# obc-v2_MCU-PinOut.net
KiCad netlist of a schematic drawn in Altium Designer
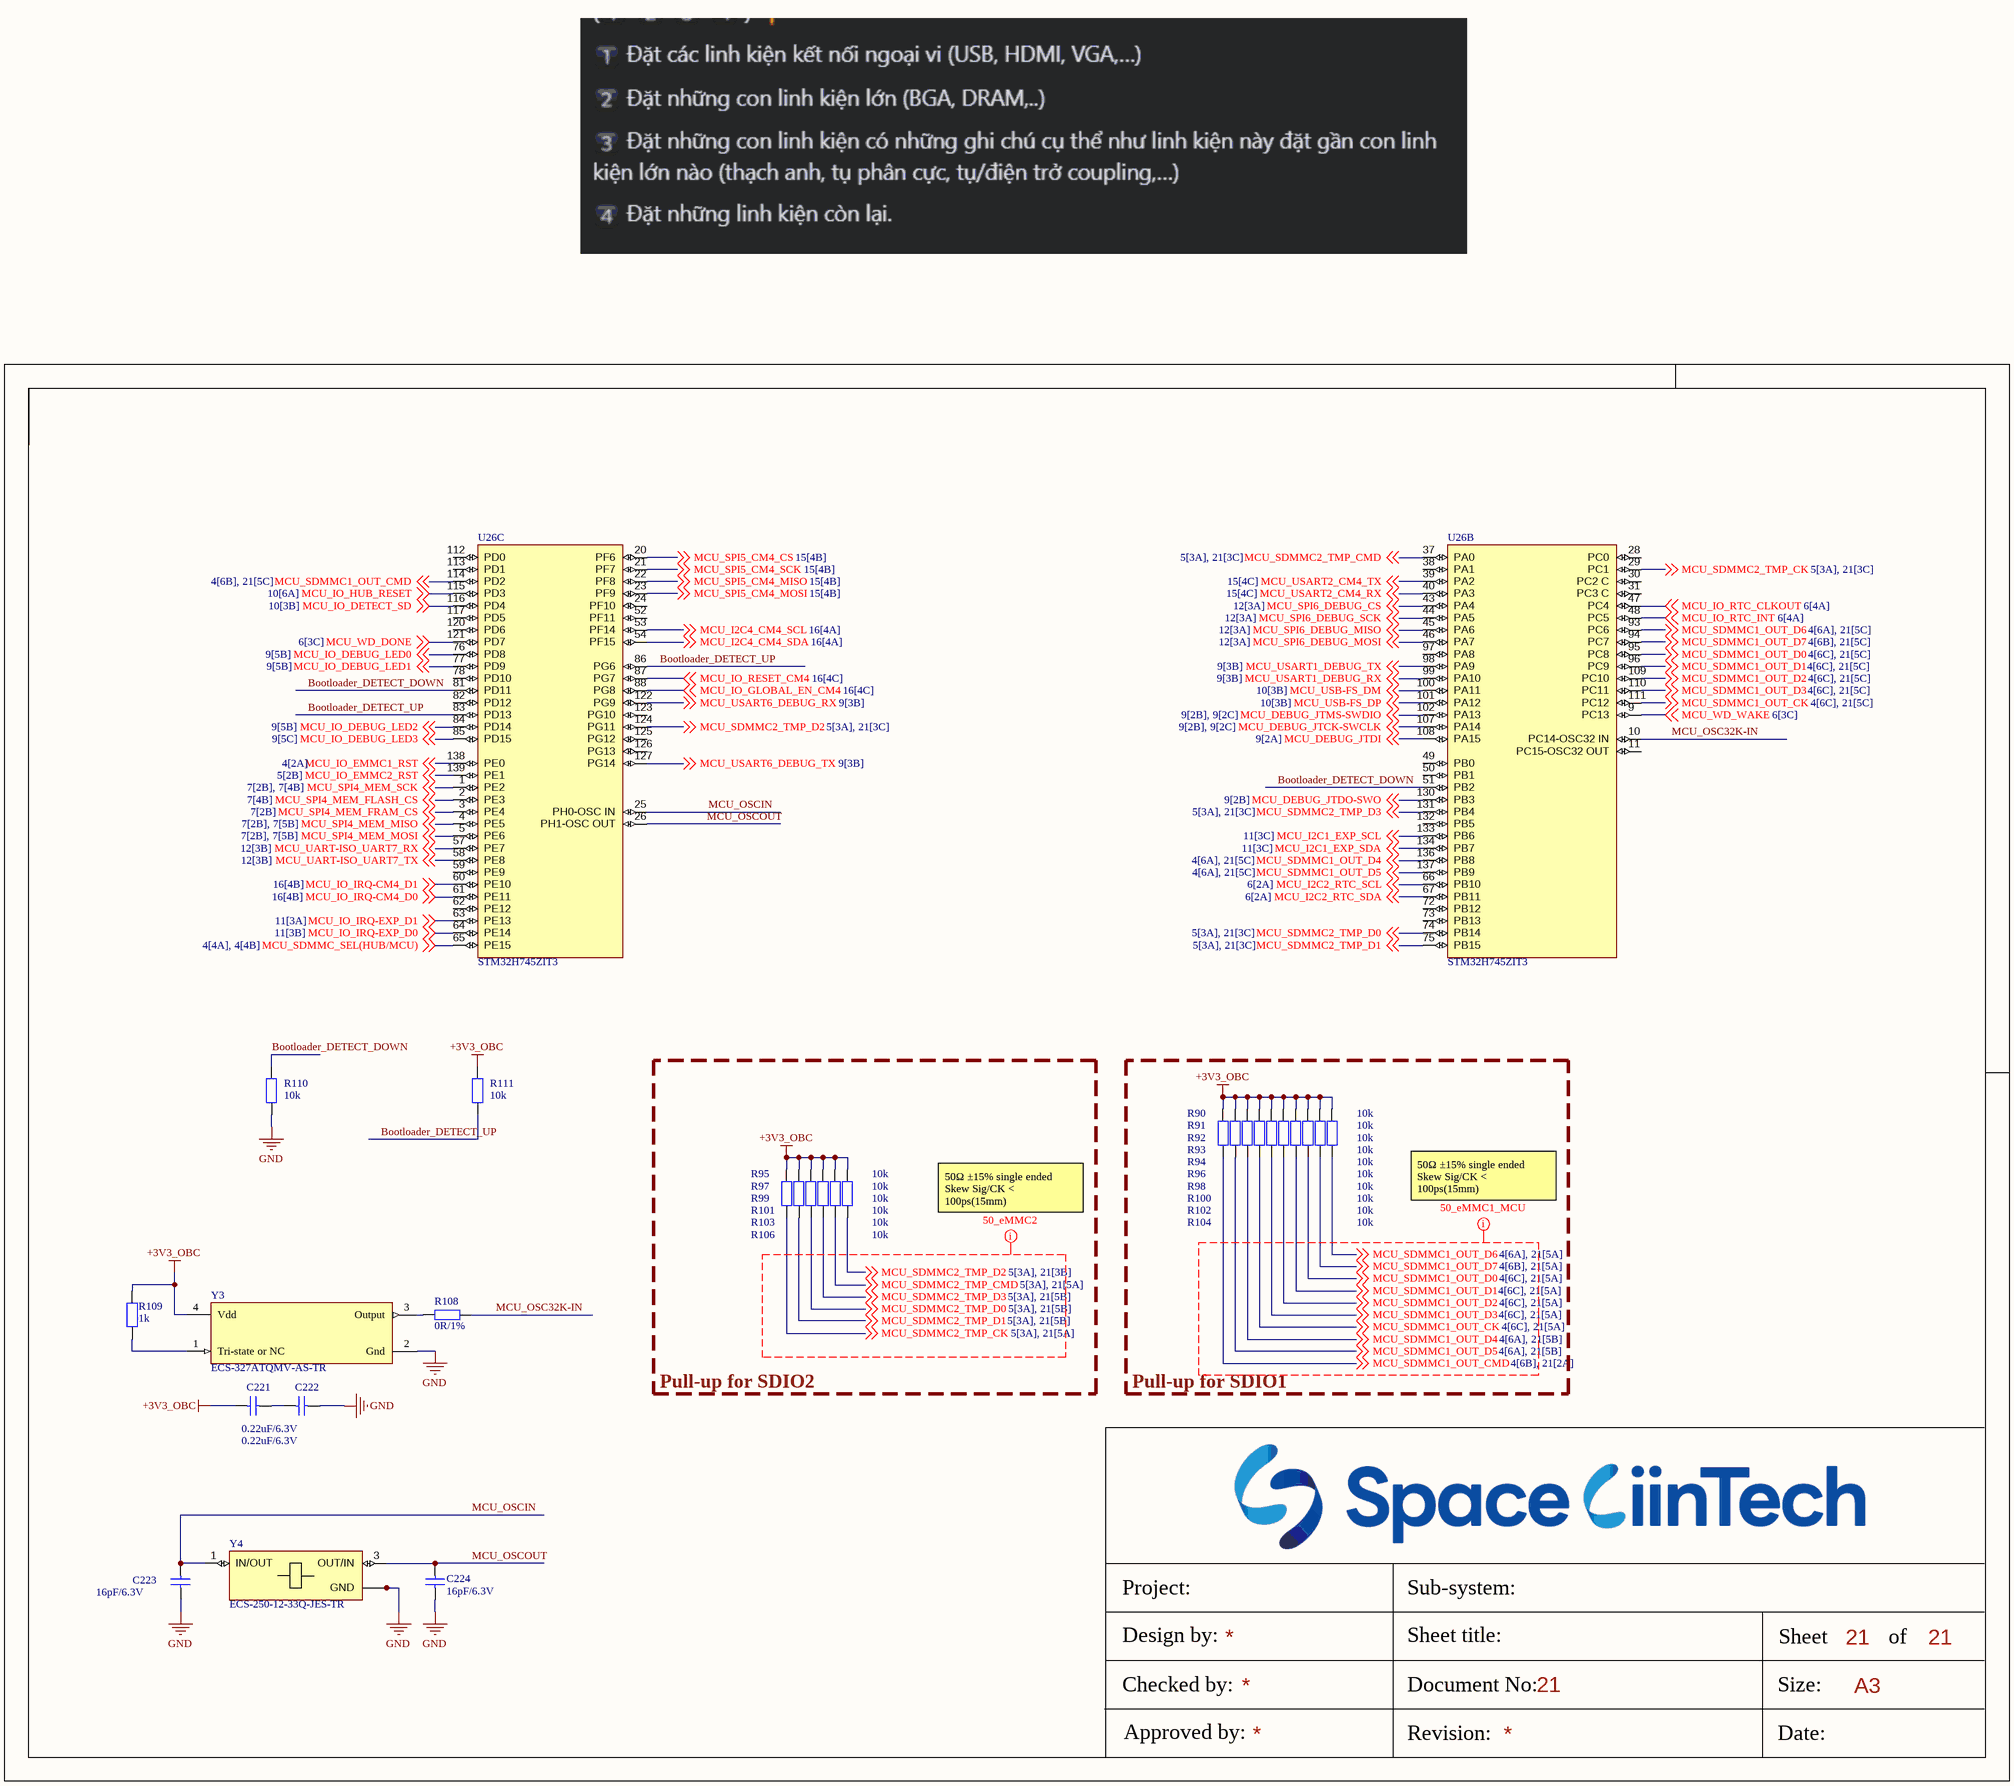
[diagram p0: obc-v2_MCU-PinOut.SchDoc]

(export (version "E")
  (design (tool "Eeschema 10.0.6"))
  (components
    (comp (ref "C221")
      (value "0.22uF/6.3V")
      (footprint "CAP_C_1005X60")
      (description "CAPC")
      (libsource (lib "Altium_Lib_by_KhueNguyenCreator") (part "Tu 0402 33nF 10V"))
    )
    (comp (ref "C222")
      (value "0.22uF/6.3V")
      (footprint "CAP_C_1005X60")
      (description "CAPC")
      (libsource (lib "Altium_Lib_by_KhueNguyenCreator") (part "Tu 0402 33nF 10V"))
    )
    (comp (ref "C223")
      (value "16pF/6.3V")
      (footprint "CAP_C_1005X60")
      (description "CAPC")
      (libsource (lib "Altium_Lib_by_KhueNguyenCreator") (part "Tu 0402 33nF 10V"))
    )
    (comp (ref "C224")
      (value "16pF/6.3V")
      (footprint "CAP_C_1005X60")
      (description "CAPC")
      (libsource (lib "Altium_Lib_by_KhueNguyenCreator") (part "Tu 0402 33nF 10V"))
    )
    (comp (ref "R90")
      (value "10k")
      (footprint "RES_C_1608X60")
      (description "RES 4.7K OHM 1% 1/10W 0603, P/N: ERJ-U03F4701V")
      (libsource (lib "Altium_Lib_by_KhueNguyenCreator") (part "Tro 0603 1% 10k"))
    )
    (comp (ref "R91")
      (value "10k")
      (footprint "RES_C_1608X60")
      (description "RES 4.7K OHM 1% 1/10W 0603, P/N: ERJ-U03F4701V")
      (libsource (lib "Altium_Lib_by_KhueNguyenCreator") (part "Tro 0603 1% 10k"))
    )
    (comp (ref "R92")
      (value "10k")
      (footprint "RES_C_1608X60")
      (description "RES 4.7K OHM 1% 1/10W 0603, P/N: ERJ-U03F4701V")
      (libsource (lib "Altium_Lib_by_KhueNguyenCreator") (part "Tro 0603 1% 10k"))
    )
    (comp (ref "R93")
      (value "10k")
      (footprint "RES_C_1608X60")
      (description "RES 4.7K OHM 1% 1/10W 0603, P/N: ERJ-U03F4701V")
      (libsource (lib "Altium_Lib_by_KhueNguyenCreator") (part "Tro 0603 1% 10k"))
    )
    (comp (ref "R94")
      (value "10k")
      (footprint "RES_C_1608X60")
      (description "RES 4.7K OHM 1% 1/10W 0603, P/N: ERJ-U03F4701V")
      (libsource (lib "Altium_Lib_by_KhueNguyenCreator") (part "Tro 0603 1% 10k"))
    )
    (comp (ref "R95")
      (value "10k")
      (footprint "RES_C_1608X60")
      (description "RES 4.7K OHM 1% 1/10W 0603, P/N: ERJ-U03F4701V")
      (libsource (lib "Altium_Lib_by_KhueNguyenCreator") (part "Tro 0603 1% 10k"))
    )
    (comp (ref "R96")
      (value "10k")
      (footprint "RES_C_1608X60")
      (description "RES 4.7K OHM 1% 1/10W 0603, P/N: ERJ-U03F4701V")
      (libsource (lib "Altium_Lib_by_KhueNguyenCreator") (part "Tro 0603 1% 10k"))
    )
    (comp (ref "R97")
      (value "10k")
      (footprint "RES_C_1608X60")
      (description "RES 4.7K OHM 1% 1/10W 0603, P/N: ERJ-U03F4701V")
      (libsource (lib "Altium_Lib_by_KhueNguyenCreator") (part "Tro 0603 1% 10k"))
    )
    (comp (ref "R98")
      (value "10k")
      (footprint "RES_C_1608X60")
      (description "RES 4.7K OHM 1% 1/10W 0603, P/N: ERJ-U03F4701V")
      (libsource (lib "Altium_Lib_by_KhueNguyenCreator") (part "Tro 0603 1% 10k"))
    )
    (comp (ref "R99")
      (value "10k")
      (footprint "RES_C_1608X60")
      (description "RES 4.7K OHM 1% 1/10W 0603, P/N: ERJ-U03F4701V")
      (libsource (lib "Altium_Lib_by_KhueNguyenCreator") (part "Tro 0603 1% 10k"))
    )
    (comp (ref "R100")
      (value "10k")
      (footprint "RES_C_1608X60")
      (description "RES 4.7K OHM 1% 1/10W 0603, P/N: ERJ-U03F4701V")
      (libsource (lib "Altium_Lib_by_KhueNguyenCreator") (part "Tro 0603 1% 10k"))
    )
    (comp (ref "R101")
      (value "10k")
      (footprint "RES_C_1608X60")
      (description "RES 4.7K OHM 1% 1/10W 0603, P/N: ERJ-U03F4701V")
      (libsource (lib "Altium_Lib_by_KhueNguyenCreator") (part "Tro 0603 1% 10k"))
    )
    (comp (ref "R102")
      (value "10k")
      (footprint "RES_C_1608X60")
      (description "RES 4.7K OHM 1% 1/10W 0603, P/N: ERJ-U03F4701V")
      (libsource (lib "Altium_Lib_by_KhueNguyenCreator") (part "Tro 0603 1% 10k"))
    )
    (comp (ref "R103")
      (value "10k")
      (footprint "RES_C_1608X60")
      (description "RES 4.7K OHM 1% 1/10W 0603, P/N: ERJ-U03F4701V")
      (libsource (lib "Altium_Lib_by_KhueNguyenCreator") (part "Tro 0603 1% 10k"))
    )
    (comp (ref "R104")
      (value "10k")
      (footprint "RES_C_1608X60")
      (description "RES 4.7K OHM 1% 1/10W 0603, P/N: ERJ-U03F4701V")
      (libsource (lib "Altium_Lib_by_KhueNguyenCreator") (part "Tro 0603 1% 10k"))
    )
    (comp (ref "R106")
      (value "10k")
      (footprint "RES_C_1608X60")
      (description "RES 4.7K OHM 1% 1/10W 0603, P/N: ERJ-U03F4701V")
      (libsource (lib "Altium_Lib_by_KhueNguyenCreator") (part "Tro 0603 1% 10k"))
    )
    (comp (ref "R108")
      (value "0R/1%")
      (footprint "RES_C_1608X60")
      (description "RES")
      (libsource (lib "Altium_Lib_by_KhueNguyenCreator") (part "Tro 0603 1% 10k"))
    )
    (comp (ref "R109")
      (value "1k")
      (footprint "RES_C_1608X60")
      (description "RES")
      (libsource (lib "Altium_Lib_by_KhueNguyenCreator") (part "Tro 0603 1% 10k"))
    )
    (comp (ref "R110")
      (value "10k")
      (footprint "RES_C_1608X60")
      (description "RES 4.7K OHM 1% 1/10W 0603, P/N: ERJ-U03F4701V")
      (libsource (lib "Altium_Lib_by_KhueNguyenCreator") (part "Tro 0603 1% 10k"))
    )
    (comp (ref "R111")
      (value "10k")
      (footprint "RES_C_1608X60")
      (description "RES 4.7K OHM 1% 1/10W 0603, P/N: ERJ-U03F4701V")
      (libsource (lib "Altium_Lib_by_KhueNguyenCreator") (part "Tro 0603 1% 10k"))
    )
    (comp (ref "U26")
      (value "STM32H745ZIT3")
      (footprint "FP-LQFP144-1A-MFG")
      (description "HIGH-PERFORMANCE AND DSP WITH DP")
      (fields
        (field (name "MANUFACTURER PART NUMBER") "STM32H745ZIT6")
        (field (name "OCTOPART") "https://octopart.com/stm32h745zit6-stmicroelectronics-100293939")
      )
      (libsource (lib "Altium Content Vault") (part "f5432ce9894f79c0085309acf87c031"))
    )
    (comp (ref "Y3")
      (value "ECS-327ATQMV-AS-TR")
      (footprint "FP-327ATQMV-MFG")
      (description "XTAL OSC XO 32.7680KHZ CMOS SMD")
      (libsource (lib "Altium Content Vault") (part "48575ee33648fc99c8f9879a7ebcfb2"))
    )
    (comp (ref "Y4")
      (value "ECS-250-12-33Q-JES-TR")
      (footprint "XTAL_ECS-250-12-33Q-JES-TR")
      (description "25 MHz Â±20ppm Crystal 12pF 40 Ohms 4-SMD, No Lead")
      (fields (field (name "MF") "ECS Inc."))
      (libsource (lib "ECS-250-12-33Q-JES-TR") (part "ECS-250-12-33Q-JES-TR"))
    )
  )
  (nets
    (net (code "1") (name "+3V3_OBC") (class "Default")
      (node (ref "C221") (pin "1") (pinfunction "1_1") (pintype "passive"))
      (node (ref "R100") (pin "2") (pinfunction "2_2") (pintype "passive"))
      (node (ref "R101") (pin "2") (pinfunction "2_2") (pintype "passive"))
      (node (ref "R102") (pin "2") (pinfunction "2_2") (pintype "passive"))
      (node (ref "R103") (pin "2") (pinfunction "2_2") (pintype "passive"))
      (node (ref "R104") (pin "2") (pinfunction "2_2") (pintype "passive"))
      (node (ref "R106") (pin "2") (pinfunction "2_2") (pintype "passive"))
      (node (ref "R109") (pin "1") (pinfunction "1_1") (pintype "passive"))
      (node (ref "R111") (pin "2") (pinfunction "2_2") (pintype "passive"))
      (node (ref "R90") (pin "2") (pinfunction "2_2") (pintype "passive"))
      (node (ref "R91") (pin "2") (pinfunction "2_2") (pintype "passive"))
      (node (ref "R92") (pin "2") (pinfunction "2_2") (pintype "passive"))
      (node (ref "R93") (pin "2") (pinfunction "2_2") (pintype "passive"))
      (node (ref "R94") (pin "2") (pinfunction "2_2") (pintype "passive"))
      (node (ref "R95") (pin "2") (pinfunction "2_2") (pintype "passive"))
      (node (ref "R96") (pin "2") (pinfunction "2_2") (pintype "passive"))
      (node (ref "R97") (pin "2") (pinfunction "2_2") (pintype "passive"))
      (node (ref "R98") (pin "2") (pinfunction "2_2") (pintype "passive"))
      (node (ref "R99") (pin "2") (pinfunction "2_2") (pintype "passive"))
      (node (ref "Y3") (pin "4") (pinfunction "Vdd_4") (pintype "power_in"))
    )
    (net (code "2") (name "/Bootloader_DETECT_DOWN") (class "Default")
      (node (ref "R110") (pin "2") (pinfunction "2_2") (pintype "passive"))
      (node (ref "U26") (pin "51") (pinfunction "PB2_51") (pintype "bidirectional"))
      (node (ref "U26") (pin "81") (pinfunction "PD11_81") (pintype "bidirectional"))
    )
    (net (code "3") (name "/Bootloader_DETECT_UP") (class "Default")
      (node (ref "R111") (pin "1") (pinfunction "1_1") (pintype "passive"))
      (node (ref "U26") (pin "83") (pinfunction "PD13_83") (pintype "bidirectional"))
      (node (ref "U26") (pin "86") (pinfunction "PG6_86") (pintype "bidirectional"))
    )
    (net (code "4") (name "/MCU_OSC32K-IN") (class "Default")
      (node (ref "R108") (pin "1") (pinfunction "1_1") (pintype "passive"))
      (node (ref "U26") (pin "10") (pinfunction "PC14-OSC32_IN_10") (pintype "bidirectional"))
    )
    (net (code "5") (name "/MCU_OSCIN") (class "Default")
      (node (ref "C223") (pin "2") (pinfunction "2_2") (pintype "passive"))
      (node (ref "U26") (pin "25") (pinfunction "PH0-OSC_IN_25") (pintype "bidirectional"))
      (node (ref "Y4") (pin "1") (pinfunction "IN/OUT_1") (pintype "bidirectional"))
    )
    (net (code "6") (name "/MCU_OSCOUT") (class "Default")
      (node (ref "C224") (pin "2") (pinfunction "2_2") (pintype "passive"))
      (node (ref "U26") (pin "26") (pinfunction "PH1-OSC_OUT_26") (pintype "bidirectional"))
      (node (ref "Y4") (pin "3") (pinfunction "OUT/IN_3") (pintype "bidirectional"))
    )
    (net (code "7") (name "GND") (class "Default")
      (node (ref "C222") (pin "2") (pinfunction "2_2") (pintype "passive"))
      (node (ref "C223") (pin "1") (pinfunction "1_1") (pintype "passive"))
      (node (ref "C224") (pin "1") (pinfunction "1_1") (pintype "passive"))
      (node (ref "R110") (pin "1") (pinfunction "1_1") (pintype "passive"))
      (node (ref "Y3") (pin "2") (pinfunction "Gnd_2") (pintype "power_in"))
      (node (ref "Y4") (pin "2") (pinfunction "GND_2") (pintype "power_in"))
      (node (ref "Y4") (pin "4") (pinfunction "GND_4") (pintype "power_in"))
    )
    (net (code "8") (name "MCU_DEBUG_JTCK-SWCLK") (class "Default")
      (node (ref "U26") (pin "107") (pinfunction "PA14_107") (pintype "bidirectional"))
    )
    (net (code "9") (name "MCU_DEBUG_JTDI") (class "Default")
      (node (ref "U26") (pin "108") (pinfunction "PA15_108") (pintype "bidirectional"))
    )
    (net (code "10") (name "MCU_DEBUG_JTDO-SWO") (class "Default")
      (node (ref "U26") (pin "130") (pinfunction "PB3_130") (pintype "bidirectional"))
    )
    (net (code "11") (name "MCU_DEBUG_JTMS-SWDIO") (class "Default")
      (node (ref "U26") (pin "102") (pinfunction "PA13_102") (pintype "bidirectional"))
    )
    (net (code "12") (name "MCU_I2C1_EXP_SCL") (class "Default")
      (node (ref "U26") (pin "133") (pinfunction "PB6_133") (pintype "bidirectional"))
    )
    (net (code "13") (name "MCU_I2C1_EXP_SDA") (class "Default")
      (node (ref "U26") (pin "134") (pinfunction "PB7_134") (pintype "bidirectional"))
    )
    (net (code "14") (name "MCU_I2C2_RTC_SCL") (class "Default")
      (node (ref "U26") (pin "66") (pinfunction "PB10_66") (pintype "bidirectional"))
    )
    (net (code "15") (name "MCU_I2C2_RTC_SDA") (class "Default")
      (node (ref "U26") (pin "67") (pinfunction "PB11_67") (pintype "bidirectional"))
    )
    (net (code "16") (name "MCU_I2C4_CM4_SCL") (class "Default")
      (node (ref "U26") (pin "53") (pinfunction "PF14_53") (pintype "bidirectional"))
    )
    (net (code "17") (name "MCU_I2C4_CM4_SDA") (class "Default")
      (node (ref "U26") (pin "54") (pinfunction "PF15_54") (pintype "bidirectional"))
    )
    (net (code "18") (name "MCU_IO_DEBUG_LED0") (class "Default")
      (node (ref "U26") (pin "76") (pinfunction "PD8_76") (pintype "bidirectional"))
    )
    (net (code "19") (name "MCU_IO_DEBUG_LED1") (class "Default")
      (node (ref "U26") (pin "77") (pinfunction "PD9_77") (pintype "bidirectional"))
    )
    (net (code "20") (name "MCU_IO_DEBUG_LED2") (class "Default")
      (node (ref "U26") (pin "84") (pinfunction "PD14_84") (pintype "bidirectional"))
    )
    (net (code "21") (name "MCU_IO_DEBUG_LED3") (class "Default")
      (node (ref "U26") (pin "85") (pinfunction "PD15_85") (pintype "bidirectional"))
    )
    (net (code "22") (name "MCU_IO_DETECT_SD") (class "Default")
      (node (ref "U26") (pin "116") (pinfunction "PD4_116") (pintype "bidirectional"))
    )
    (net (code "23") (name "MCU_IO_EMMC1_RST") (class "Default")
      (node (ref "U26") (pin "138") (pinfunction "PE0_138") (pintype "bidirectional"))
    )
    (net (code "24") (name "MCU_IO_EMMC2_RST") (class "Default")
      (node (ref "U26") (pin "139") (pinfunction "PE1_139") (pintype "bidirectional"))
    )
    (net (code "25") (name "MCU_IO_GLOBAL_EN_CM4") (class "Default")
      (node (ref "U26") (pin "88") (pinfunction "PG8_88") (pintype "bidirectional"))
    )
    (net (code "26") (name "MCU_IO_HUB_RESET") (class "Default")
      (node (ref "U26") (pin "115") (pinfunction "PD3_115") (pintype "bidirectional"))
    )
    (net (code "27") (name "MCU_IO_IRQ-CM4_D0") (class "Default")
      (node (ref "U26") (pin "61") (pinfunction "PE11_61") (pintype "bidirectional"))
    )
    (net (code "28") (name "MCU_IO_IRQ-CM4_D1") (class "Default")
      (node (ref "U26") (pin "60") (pinfunction "PE10_60") (pintype "bidirectional"))
    )
    (net (code "29") (name "MCU_IO_IRQ-EXP_D0") (class "Default")
      (node (ref "U26") (pin "64") (pinfunction "PE14_64") (pintype "bidirectional"))
    )
    (net (code "30") (name "MCU_IO_IRQ-EXP_D1") (class "Default")
      (node (ref "U26") (pin "63") (pinfunction "PE13_63") (pintype "bidirectional"))
    )
    (net (code "31") (name "MCU_IO_RESET_CM4") (class "Default")
      (node (ref "U26") (pin "87") (pinfunction "PG7_87") (pintype "bidirectional"))
    )
    (net (code "32") (name "MCU_IO_RTC_CLKOUT") (class "Default")
      (node (ref "U26") (pin "47") (pinfunction "PC4_47") (pintype "bidirectional"))
    )
    (net (code "33") (name "MCU_IO_RTC_INT") (class "Default")
      (node (ref "U26") (pin "48") (pinfunction "PC5_48") (pintype "bidirectional"))
    )
    (net (code "34") (name "MCU_SDMMC1_OUT_CK") (class "Default")
      (node (ref "R93") (pin "1") (pinfunction "1_1") (pintype "passive"))
      (node (ref "U26") (pin "111") (pinfunction "PC12_111") (pintype "bidirectional"))
    )
    (net (code "35") (name "MCU_SDMMC1_OUT_CMD") (class "Default")
      (node (ref "R90") (pin "1") (pinfunction "1_1") (pintype "passive"))
      (node (ref "U26") (pin "114") (pinfunction "PD2_114") (pintype "bidirectional"))
    )
    (net (code "36") (name "MCU_SDMMC1_OUT_D0") (class "Default")
      (node (ref "R100") (pin "1") (pinfunction "1_1") (pintype "passive"))
      (node (ref "U26") (pin "95") (pinfunction "PC8_95") (pintype "bidirectional"))
    )
    (net (code "37") (name "MCU_SDMMC1_OUT_D1") (class "Default")
      (node (ref "R98") (pin "1") (pinfunction "1_1") (pintype "passive"))
      (node (ref "U26") (pin "96") (pinfunction "PC9_96") (pintype "bidirectional"))
    )
    (net (code "38") (name "MCU_SDMMC1_OUT_D2") (class "Default")
      (node (ref "R96") (pin "1") (pinfunction "1_1") (pintype "passive"))
      (node (ref "U26") (pin "109") (pinfunction "PC10_109") (pintype "bidirectional"))
    )
    (net (code "39") (name "MCU_SDMMC1_OUT_D3") (class "Default")
      (node (ref "R94") (pin "1") (pinfunction "1_1") (pintype "passive"))
      (node (ref "U26") (pin "110") (pinfunction "PC11_110") (pintype "bidirectional"))
    )
    (net (code "40") (name "MCU_SDMMC1_OUT_D4") (class "Default")
      (node (ref "R92") (pin "1") (pinfunction "1_1") (pintype "passive"))
      (node (ref "U26") (pin "136") (pinfunction "PB8_136") (pintype "bidirectional"))
    )
    (net (code "41") (name "MCU_SDMMC1_OUT_D5") (class "Default")
      (node (ref "R91") (pin "1") (pinfunction "1_1") (pintype "passive"))
      (node (ref "U26") (pin "137") (pinfunction "PB9_137") (pintype "bidirectional"))
    )
    (net (code "42") (name "MCU_SDMMC1_OUT_D6") (class "Default")
      (node (ref "R104") (pin "1") (pinfunction "1_1") (pintype "passive"))
      (node (ref "U26") (pin "93") (pinfunction "PC6_93") (pintype "bidirectional"))
    )
    (net (code "43") (name "MCU_SDMMC1_OUT_D7") (class "Default")
      (node (ref "R102") (pin "1") (pinfunction "1_1") (pintype "passive"))
      (node (ref "U26") (pin "94") (pinfunction "PC7_94") (pintype "bidirectional"))
    )
    (net (code "44") (name "MCU_SDMMC2_TMP_CK") (class "Default")
      (node (ref "R95") (pin "1") (pinfunction "1_1") (pintype "passive"))
      (node (ref "U26") (pin "29") (pinfunction "PC1_29") (pintype "bidirectional"))
    )
    (net (code "45") (name "MCU_SDMMC2_TMP_CMD") (class "Default")
      (node (ref "R103") (pin "1") (pinfunction "1_1") (pintype "passive"))
      (node (ref "U26") (pin "37") (pinfunction "PA0_37") (pintype "bidirectional"))
    )
    (net (code "46") (name "MCU_SDMMC2_TMP_D0") (class "Default")
      (node (ref "R99") (pin "1") (pinfunction "1_1") (pintype "passive"))
      (node (ref "U26") (pin "74") (pinfunction "PB14_74") (pintype "bidirectional"))
    )
    (net (code "47") (name "MCU_SDMMC2_TMP_D1") (class "Default")
      (node (ref "R97") (pin "1") (pinfunction "1_1") (pintype "passive"))
      (node (ref "U26") (pin "75") (pinfunction "PB15_75") (pintype "bidirectional"))
    )
    (net (code "48") (name "MCU_SDMMC2_TMP_D2") (class "Default")
      (node (ref "R106") (pin "1") (pinfunction "1_1") (pintype "passive"))
      (node (ref "U26") (pin "124") (pinfunction "PG11_124") (pintype "bidirectional"))
    )
    (net (code "49") (name "MCU_SDMMC2_TMP_D3") (class "Default")
      (node (ref "R101") (pin "1") (pinfunction "1_1") (pintype "passive"))
      (node (ref "U26") (pin "131") (pinfunction "PB4_131") (pintype "bidirectional"))
    )
    (net (code "50") (name "MCU_SDMMC_SEL(HUB{slash}MCU)") (class "Default")
      (node (ref "U26") (pin "65") (pinfunction "PE15_65") (pintype "bidirectional"))
    )
    (net (code "51") (name "MCU_SPI4_MEM_FLASH_CS") (class "Default")
      (node (ref "U26") (pin "2") (pinfunction "PE3_2") (pintype "bidirectional"))
    )
    (net (code "52") (name "MCU_SPI4_MEM_FRAM_CS") (class "Default")
      (node (ref "U26") (pin "3") (pinfunction "PE4_3") (pintype "bidirectional"))
    )
    (net (code "53") (name "MCU_SPI4_MEM_MISO") (class "Default")
      (node (ref "U26") (pin "4") (pinfunction "PE5_4") (pintype "bidirectional"))
    )
    (net (code "54") (name "MCU_SPI4_MEM_MOSI") (class "Default")
      (node (ref "U26") (pin "5") (pinfunction "PE6_5") (pintype "bidirectional"))
    )
    (net (code "55") (name "MCU_SPI4_MEM_SCK") (class "Default")
      (node (ref "U26") (pin "1") (pinfunction "PE2_1") (pintype "bidirectional"))
    )
    (net (code "56") (name "MCU_SPI5_CM4_CS") (class "Default")
      (node (ref "U26") (pin "20") (pinfunction "PF6_20") (pintype "bidirectional"))
    )
    (net (code "57") (name "MCU_SPI5_CM4_MISO") (class "Default")
      (node (ref "U26") (pin "22") (pinfunction "PF8_22") (pintype "bidirectional"))
    )
    (net (code "58") (name "MCU_SPI5_CM4_MOSI") (class "Default")
      (node (ref "U26") (pin "23") (pinfunction "PF9_23") (pintype "bidirectional"))
    )
    (net (code "59") (name "MCU_SPI5_CM4_SCK") (class "Default")
      (node (ref "U26") (pin "21") (pinfunction "PF7_21") (pintype "bidirectional"))
    )
    (net (code "60") (name "MCU_SPI6_DEBUG_CS") (class "Default")
      (node (ref "U26") (pin "43") (pinfunction "PA4_43") (pintype "bidirectional"))
    )
    (net (code "61") (name "MCU_SPI6_DEBUG_MISO") (class "Default")
      (node (ref "U26") (pin "45") (pinfunction "PA6_45") (pintype "bidirectional"))
    )
    (net (code "62") (name "MCU_SPI6_DEBUG_MOSI") (class "Default")
      (node (ref "U26") (pin "46") (pinfunction "PA7_46") (pintype "bidirectional"))
    )
    (net (code "63") (name "MCU_SPI6_DEBUG_SCK") (class "Default")
      (node (ref "U26") (pin "44") (pinfunction "PA5_44") (pintype "bidirectional"))
    )
    (net (code "64") (name "MCU_UART-ISO_UART7_RX") (class "Default")
      (node (ref "U26") (pin "57") (pinfunction "PE7_57") (pintype "bidirectional"))
    )
    (net (code "65") (name "MCU_UART-ISO_UART7_TX") (class "Default")
      (node (ref "U26") (pin "58") (pinfunction "PE8_58") (pintype "bidirectional"))
    )
    (net (code "66") (name "MCU_USART1_DEBUG_RX") (class "Default")
      (node (ref "U26") (pin "99") (pinfunction "PA10_99") (pintype "bidirectional"))
    )
    (net (code "67") (name "MCU_USART1_DEBUG_TX") (class "Default")
      (node (ref "U26") (pin "98") (pinfunction "PA9_98") (pintype "bidirectional"))
    )
    (net (code "68") (name "MCU_USART2_CM4_RX") (class "Default")
      (node (ref "U26") (pin "40") (pinfunction "PA3_40") (pintype "bidirectional"))
    )
    (net (code "69") (name "MCU_USART2_CM4_TX") (class "Default")
      (node (ref "U26") (pin "39") (pinfunction "PA2_39") (pintype "bidirectional"))
    )
    (net (code "70") (name "MCU_USART6_DEBUG_RX") (class "Default")
      (node (ref "U26") (pin "122") (pinfunction "PG9_122") (pintype "bidirectional"))
    )
    (net (code "71") (name "MCU_USART6_DEBUG_TX") (class "Default")
      (node (ref "U26") (pin "127") (pinfunction "PG14_127") (pintype "bidirectional"))
    )
    (net (code "72") (name "MCU_USB-FS_DM") (class "Default")
      (node (ref "U26") (pin "100") (pinfunction "PA11_100") (pintype "bidirectional"))
    )
    (net (code "73") (name "MCU_USB-FS_DP") (class "Default")
      (node (ref "U26") (pin "101") (pinfunction "PA12_101") (pintype "bidirectional"))
    )
    (net (code "74") (name "MCU_WD_DONE") (class "Default")
      (node (ref "U26") (pin "121") (pinfunction "PD7_121") (pintype "bidirectional"))
    )
    (net (code "75") (name "MCU_WD_WAKE") (class "Default")
      (node (ref "U26") (pin "9") (pinfunction "PC13_9") (pintype "bidirectional"))
    )
    (net (code "76") (name "Net-(C221-Pad2)") (class "Default")
      (node (ref "C221") (pin "2") (pinfunction "2_2") (pintype "passive"))
      (node (ref "C222") (pin "1") (pinfunction "1_1") (pintype "passive"))
    )
    (net (code "77") (name "Net-(Y3-Output)") (class "Default")
      (node (ref "R108") (pin "2") (pinfunction "2_2") (pintype "passive"))
      (node (ref "Y3") (pin "3") (pinfunction "Output_3") (pintype "output"))
    )
    (net (code "78") (name "Net-(Y3-Tri-state_or_NC)") (class "Default")
      (node (ref "R109") (pin "2") (pinfunction "2_2") (pintype "passive"))
      (node (ref "Y3") (pin "1") (pinfunction "Tri-state_or_NC_1") (pintype "input"))
    )
    (net (code "79") (name "unconnected-(U26B-PA1-Pad38)") (class "Default")
      (node (ref "U26") (pin "38") (pinfunction "PA1_38") (pintype "bidirectional"))
    )
    (net (code "80") (name "unconnected-(U26B-PA8-Pad97)") (class "Default")
      (node (ref "U26") (pin "97") (pinfunction "PA8_97") (pintype "bidirectional"))
    )
    (net (code "81") (name "unconnected-(U26B-PB0-Pad49)") (class "Default")
      (node (ref "U26") (pin "49") (pinfunction "PB0_49") (pintype "bidirectional"))
    )
    (net (code "82") (name "unconnected-(U26B-PB1-Pad50)") (class "Default")
      (node (ref "U26") (pin "50") (pinfunction "PB1_50") (pintype "bidirectional"))
    )
    (net (code "83") (name "unconnected-(U26B-PB5-Pad132)") (class "Default")
      (node (ref "U26") (pin "132") (pinfunction "PB5_132") (pintype "bidirectional"))
    )
    (net (code "84") (name "unconnected-(U26B-PB12-Pad72)") (class "Default")
      (node (ref "U26") (pin "72") (pinfunction "PB12_72") (pintype "bidirectional"))
    )
    (net (code "85") (name "unconnected-(U26B-PB13-Pad73)") (class "Default")
      (node (ref "U26") (pin "73") (pinfunction "PB13_73") (pintype "bidirectional"))
    )
    (net (code "86") (name "unconnected-(U26B-PC0-Pad28)") (class "Default")
      (node (ref "U26") (pin "28") (pinfunction "PC0_28") (pintype "bidirectional"))
    )
    (net (code "87") (name "unconnected-(U26B-PC2_C-Pad30)") (class "Default")
      (node (ref "U26") (pin "30") (pinfunction "PC2_C_30") (pintype "bidirectional"))
    )
    (net (code "88") (name "unconnected-(U26B-PC3_C-Pad31)") (class "Default")
      (node (ref "U26") (pin "31") (pinfunction "PC3_C_31") (pintype "bidirectional"))
    )
    (net (code "89") (name "unconnected-(U26B-PC15-OSC32_OUT-Pad11)") (class "Default")
      (node (ref "U26") (pin "11") (pinfunction "PC15-OSC32_OUT_11") (pintype "bidirectional"))
    )
    (net (code "90") (name "unconnected-(U26C-PD0-Pad112)") (class "Default")
      (node (ref "U26") (pin "112") (pinfunction "PD0_112") (pintype "bidirectional"))
    )
    (net (code "91") (name "unconnected-(U26C-PD1-Pad113)") (class "Default")
      (node (ref "U26") (pin "113") (pinfunction "PD1_113") (pintype "bidirectional"))
    )
    (net (code "92") (name "unconnected-(U26C-PD5-Pad117)") (class "Default")
      (node (ref "U26") (pin "117") (pinfunction "PD5_117") (pintype "bidirectional"))
    )
    (net (code "93") (name "unconnected-(U26C-PD6-Pad120)") (class "Default")
      (node (ref "U26") (pin "120") (pinfunction "PD6_120") (pintype "bidirectional"))
    )
    (net (code "94") (name "unconnected-(U26C-PD10-Pad78)") (class "Default")
      (node (ref "U26") (pin "78") (pinfunction "PD10_78") (pintype "bidirectional"))
    )
    (net (code "95") (name "unconnected-(U26C-PD12-Pad82)") (class "Default")
      (node (ref "U26") (pin "82") (pinfunction "PD12_82") (pintype "bidirectional"))
    )
    (net (code "96") (name "unconnected-(U26C-PE9-Pad59)") (class "Default")
      (node (ref "U26") (pin "59") (pinfunction "PE9_59") (pintype "bidirectional"))
    )
    (net (code "97") (name "unconnected-(U26C-PE12-Pad62)") (class "Default")
      (node (ref "U26") (pin "62") (pinfunction "PE12_62") (pintype "bidirectional"))
    )
    (net (code "98") (name "unconnected-(U26C-PF10-Pad24)") (class "Default")
      (node (ref "U26") (pin "24") (pinfunction "PF10_24") (pintype "bidirectional"))
    )
    (net (code "99") (name "unconnected-(U26C-PF11-Pad52)") (class "Default")
      (node (ref "U26") (pin "52") (pinfunction "PF11_52") (pintype "bidirectional"))
    )
    (net (code "100") (name "unconnected-(U26C-PG10-Pad123)") (class "Default")
      (node (ref "U26") (pin "123") (pinfunction "PG10_123") (pintype "bidirectional"))
    )
    (net (code "101") (name "unconnected-(U26C-PG12-Pad125)") (class "Default")
      (node (ref "U26") (pin "125") (pinfunction "PG12_125") (pintype "bidirectional"))
    )
    (net (code "102") (name "unconnected-(U26C-PG13-Pad126)") (class "Default")
      (node (ref "U26") (pin "126") (pinfunction "PG13_126") (pintype "bidirectional"))
    )
  )
)
